# Intento_de_pcb.net
KiCad netlist of a schematic drawn in EAGLE
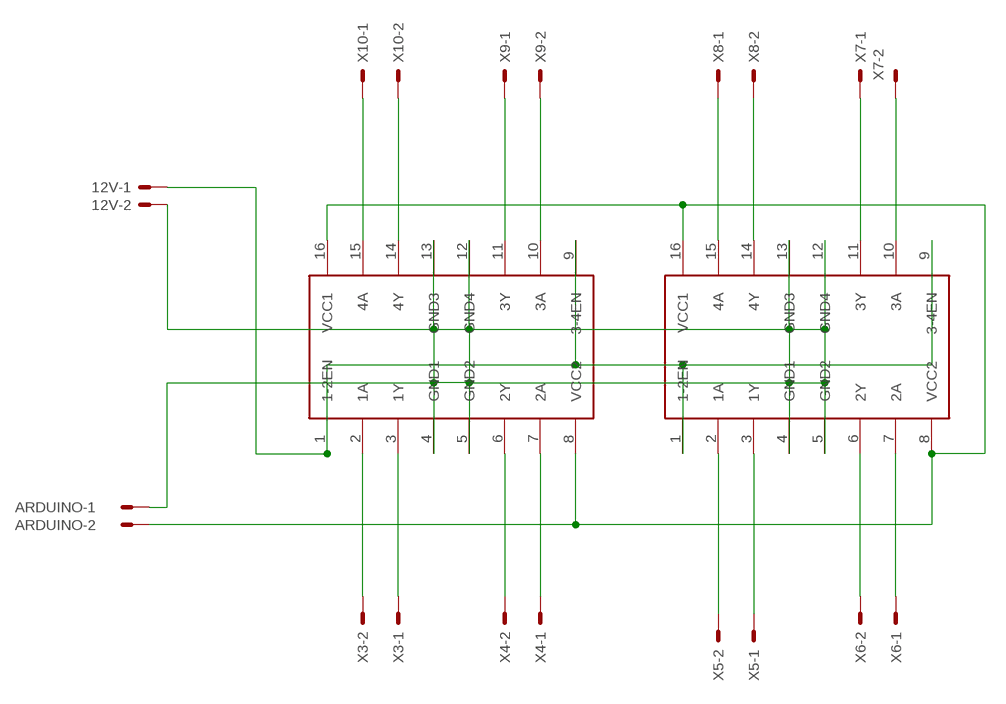
[diagram p0: schematic, sheet 1]

(export (version "E")
  (design (tool "Eeschema 10.0.6"))
  (components
    (comp (ref "12V")
      (value "22-23-2021")
      (footprint "eagle-import:22-23-2021")
      (fields (field (name "MF") "MOLEX"))
      (libsource (lib "eagle-import") (part "22-23-2021"))
    )
    (comp (ref "ARDUINO")
      (value "22-23-2021")
      (footprint "eagle-import:22-23-2021")
      (fields (field (name "MF") "MOLEX"))
      (libsource (lib "eagle-import") (part "22-23-2021"))
    )
    (comp (ref "IC1")
      (value "L293D")
      (footprint "eagle-import:DIL16")
      (libsource (lib "eagle-import") (part "L293D"))
    )
    (comp (ref "IC2")
      (value "L293D")
      (footprint "eagle-import:DIL16")
      (libsource (lib "eagle-import") (part "L293D"))
    )
    (comp (ref "X3")
      (value "22-23-2021")
      (footprint "eagle-import:22-23-2021")
      (fields (field (name "MF") "MOLEX"))
      (libsource (lib "eagle-import") (part "22-23-2021"))
    )
    (comp (ref "X4")
      (value "22-23-2021")
      (footprint "eagle-import:22-23-2021")
      (fields (field (name "MF") "MOLEX"))
      (libsource (lib "eagle-import") (part "22-23-2021"))
    )
    (comp (ref "X5")
      (value "22-23-2021")
      (footprint "eagle-import:22-23-2021")
      (fields (field (name "MF") "MOLEX"))
      (libsource (lib "eagle-import") (part "22-23-2021"))
    )
    (comp (ref "X6")
      (value "22-23-2021")
      (footprint "eagle-import:22-23-2021")
      (fields (field (name "MF") "MOLEX"))
      (libsource (lib "eagle-import") (part "22-23-2021"))
    )
    (comp (ref "X7")
      (value "22-23-2021")
      (footprint "eagle-import:22-23-2021")
      (fields (field (name "MF") "MOLEX"))
      (libsource (lib "eagle-import") (part "22-23-2021"))
    )
    (comp (ref "X8")
      (value "22-23-2021")
      (footprint "eagle-import:22-23-2021")
      (fields (field (name "MF") "MOLEX"))
      (libsource (lib "eagle-import") (part "22-23-2021"))
    )
    (comp (ref "X9")
      (value "22-23-2021")
      (footprint "eagle-import:22-23-2021")
      (fields (field (name "MF") "MOLEX"))
      (libsource (lib "eagle-import") (part "22-23-2021"))
    )
    (comp (ref "X10")
      (value "22-23-2021")
      (footprint "eagle-import:22-23-2021")
      (fields (field (name "MF") "MOLEX"))
      (libsource (lib "eagle-import") (part "22-23-2021"))
    )
  )
  (nets
    (net (code "1") (name "Net-(12VA-S)") (class "Default")
      (node (ref "12V") (pin "1") (pinfunction "S_1") (pintype "passive"))
      (node (ref "IC1") (pin "1") (pinfunction "1-2EN_1") (pintype "input"))
      (node (ref "IC1") (pin "9") (pinfunction "3-4EN_9") (pintype "input"))
      (node (ref "IC2") (pin "1") (pinfunction "1-2EN_1") (pintype "input"))
      (node (ref "IC2") (pin "9") (pinfunction "3-4EN_9") (pintype "input"))
    )
    (net (code "2") (name "Net-(12VB-S)") (class "Default")
      (node (ref "12V") (pin "2") (pinfunction "S_2") (pintype "passive"))
      (node (ref "ARDUINO") (pin "1") (pinfunction "S_1") (pintype "passive"))
      (node (ref "IC1") (pin "12") (pinfunction "GND4_12") (pintype "power_in"))
      (node (ref "IC1") (pin "13") (pinfunction "GND3_13") (pintype "power_in"))
      (node (ref "IC1") (pin "4") (pinfunction "GND1_4") (pintype "power_in"))
      (node (ref "IC1") (pin "5") (pinfunction "GND2_5") (pintype "power_in"))
      (node (ref "IC2") (pin "12") (pinfunction "GND4_12") (pintype "power_in"))
      (node (ref "IC2") (pin "13") (pinfunction "GND3_13") (pintype "power_in"))
      (node (ref "IC2") (pin "4") (pinfunction "GND1_4") (pintype "power_in"))
      (node (ref "IC2") (pin "5") (pinfunction "GND2_5") (pintype "power_in"))
    )
    (net (code "3") (name "Net-(ARDUINOB-S)") (class "Default")
      (node (ref "ARDUINO") (pin "2") (pinfunction "S_2") (pintype "passive"))
      (node (ref "IC1") (pin "16") (pinfunction "VCC1_16") (pintype "power_in"))
      (node (ref "IC1") (pin "8") (pinfunction "VCC2_8") (pintype "power_in"))
      (node (ref "IC2") (pin "16") (pinfunction "VCC1_16") (pintype "power_in"))
      (node (ref "IC2") (pin "8") (pinfunction "VCC2_8") (pintype "power_in"))
    )
    (net (code "4") (name "Net-(IC1-1A)") (class "Default")
      (node (ref "IC1") (pin "2") (pinfunction "1A_2") (pintype "input"))
      (node (ref "X3") (pin "2") (pinfunction "S_2") (pintype "passive"))
    )
    (net (code "5") (name "Net-(IC1-1Y)") (class "Default")
      (node (ref "IC1") (pin "3") (pinfunction "1Y_3") (pintype "output"))
      (node (ref "X3") (pin "1") (pinfunction "S_1") (pintype "passive"))
    )
    (net (code "6") (name "Net-(IC1-2A)") (class "Default")
      (node (ref "IC1") (pin "7") (pinfunction "2A_7") (pintype "input"))
      (node (ref "X4") (pin "1") (pinfunction "S_1") (pintype "passive"))
    )
    (net (code "7") (name "Net-(IC1-2Y)") (class "Default")
      (node (ref "IC1") (pin "6") (pinfunction "2Y_6") (pintype "output"))
      (node (ref "X4") (pin "2") (pinfunction "S_2") (pintype "passive"))
    )
    (net (code "8") (name "Net-(IC1-3A)") (class "Default")
      (node (ref "IC1") (pin "10") (pinfunction "3A_10") (pintype "input"))
      (node (ref "X9") (pin "2") (pinfunction "S_2") (pintype "passive"))
    )
    (net (code "9") (name "Net-(IC1-3Y)") (class "Default")
      (node (ref "IC1") (pin "11") (pinfunction "3Y_11") (pintype "output"))
      (node (ref "X9") (pin "1") (pinfunction "S_1") (pintype "passive"))
    )
    (net (code "10") (name "Net-(IC1-4A)") (class "Default")
      (node (ref "IC1") (pin "15") (pinfunction "4A_15") (pintype "input"))
      (node (ref "X10") (pin "1") (pinfunction "S_1") (pintype "passive"))
    )
    (net (code "11") (name "Net-(IC1-4Y)") (class "Default")
      (node (ref "IC1") (pin "14") (pinfunction "4Y_14") (pintype "output"))
      (node (ref "X10") (pin "2") (pinfunction "S_2") (pintype "passive"))
    )
    (net (code "12") (name "Net-(IC2-1A)") (class "Default")
      (node (ref "IC2") (pin "2") (pinfunction "1A_2") (pintype "input"))
      (node (ref "X5") (pin "2") (pinfunction "S_2") (pintype "passive"))
    )
    (net (code "13") (name "Net-(IC2-1Y)") (class "Default")
      (node (ref "IC2") (pin "3") (pinfunction "1Y_3") (pintype "output"))
      (node (ref "X5") (pin "1") (pinfunction "S_1") (pintype "passive"))
    )
    (net (code "14") (name "Net-(IC2-2A)") (class "Default")
      (node (ref "IC2") (pin "7") (pinfunction "2A_7") (pintype "input"))
      (node (ref "X6") (pin "1") (pinfunction "S_1") (pintype "passive"))
    )
    (net (code "15") (name "Net-(IC2-2Y)") (class "Default")
      (node (ref "IC2") (pin "6") (pinfunction "2Y_6") (pintype "output"))
      (node (ref "X6") (pin "2") (pinfunction "S_2") (pintype "passive"))
    )
    (net (code "16") (name "Net-(IC2-3A)") (class "Default")
      (node (ref "IC2") (pin "10") (pinfunction "3A_10") (pintype "input"))
      (node (ref "X7") (pin "2") (pinfunction "S_2") (pintype "passive"))
    )
    (net (code "17") (name "Net-(IC2-3Y)") (class "Default")
      (node (ref "IC2") (pin "11") (pinfunction "3Y_11") (pintype "output"))
      (node (ref "X7") (pin "1") (pinfunction "S_1") (pintype "passive"))
    )
    (net (code "18") (name "Net-(IC2-4A)") (class "Default")
      (node (ref "IC2") (pin "15") (pinfunction "4A_15") (pintype "input"))
      (node (ref "X8") (pin "1") (pinfunction "S_1") (pintype "passive"))
    )
    (net (code "19") (name "Net-(IC2-4Y)") (class "Default")
      (node (ref "IC2") (pin "14") (pinfunction "4Y_14") (pintype "output"))
      (node (ref "X8") (pin "2") (pinfunction "S_2") (pintype "passive"))
    )
  )
)
